# 780-00020_rev_2_pg1_Two_Axis_Stepper_Dri.net
KiCad netlist of a schematic drawn in Altium Designer
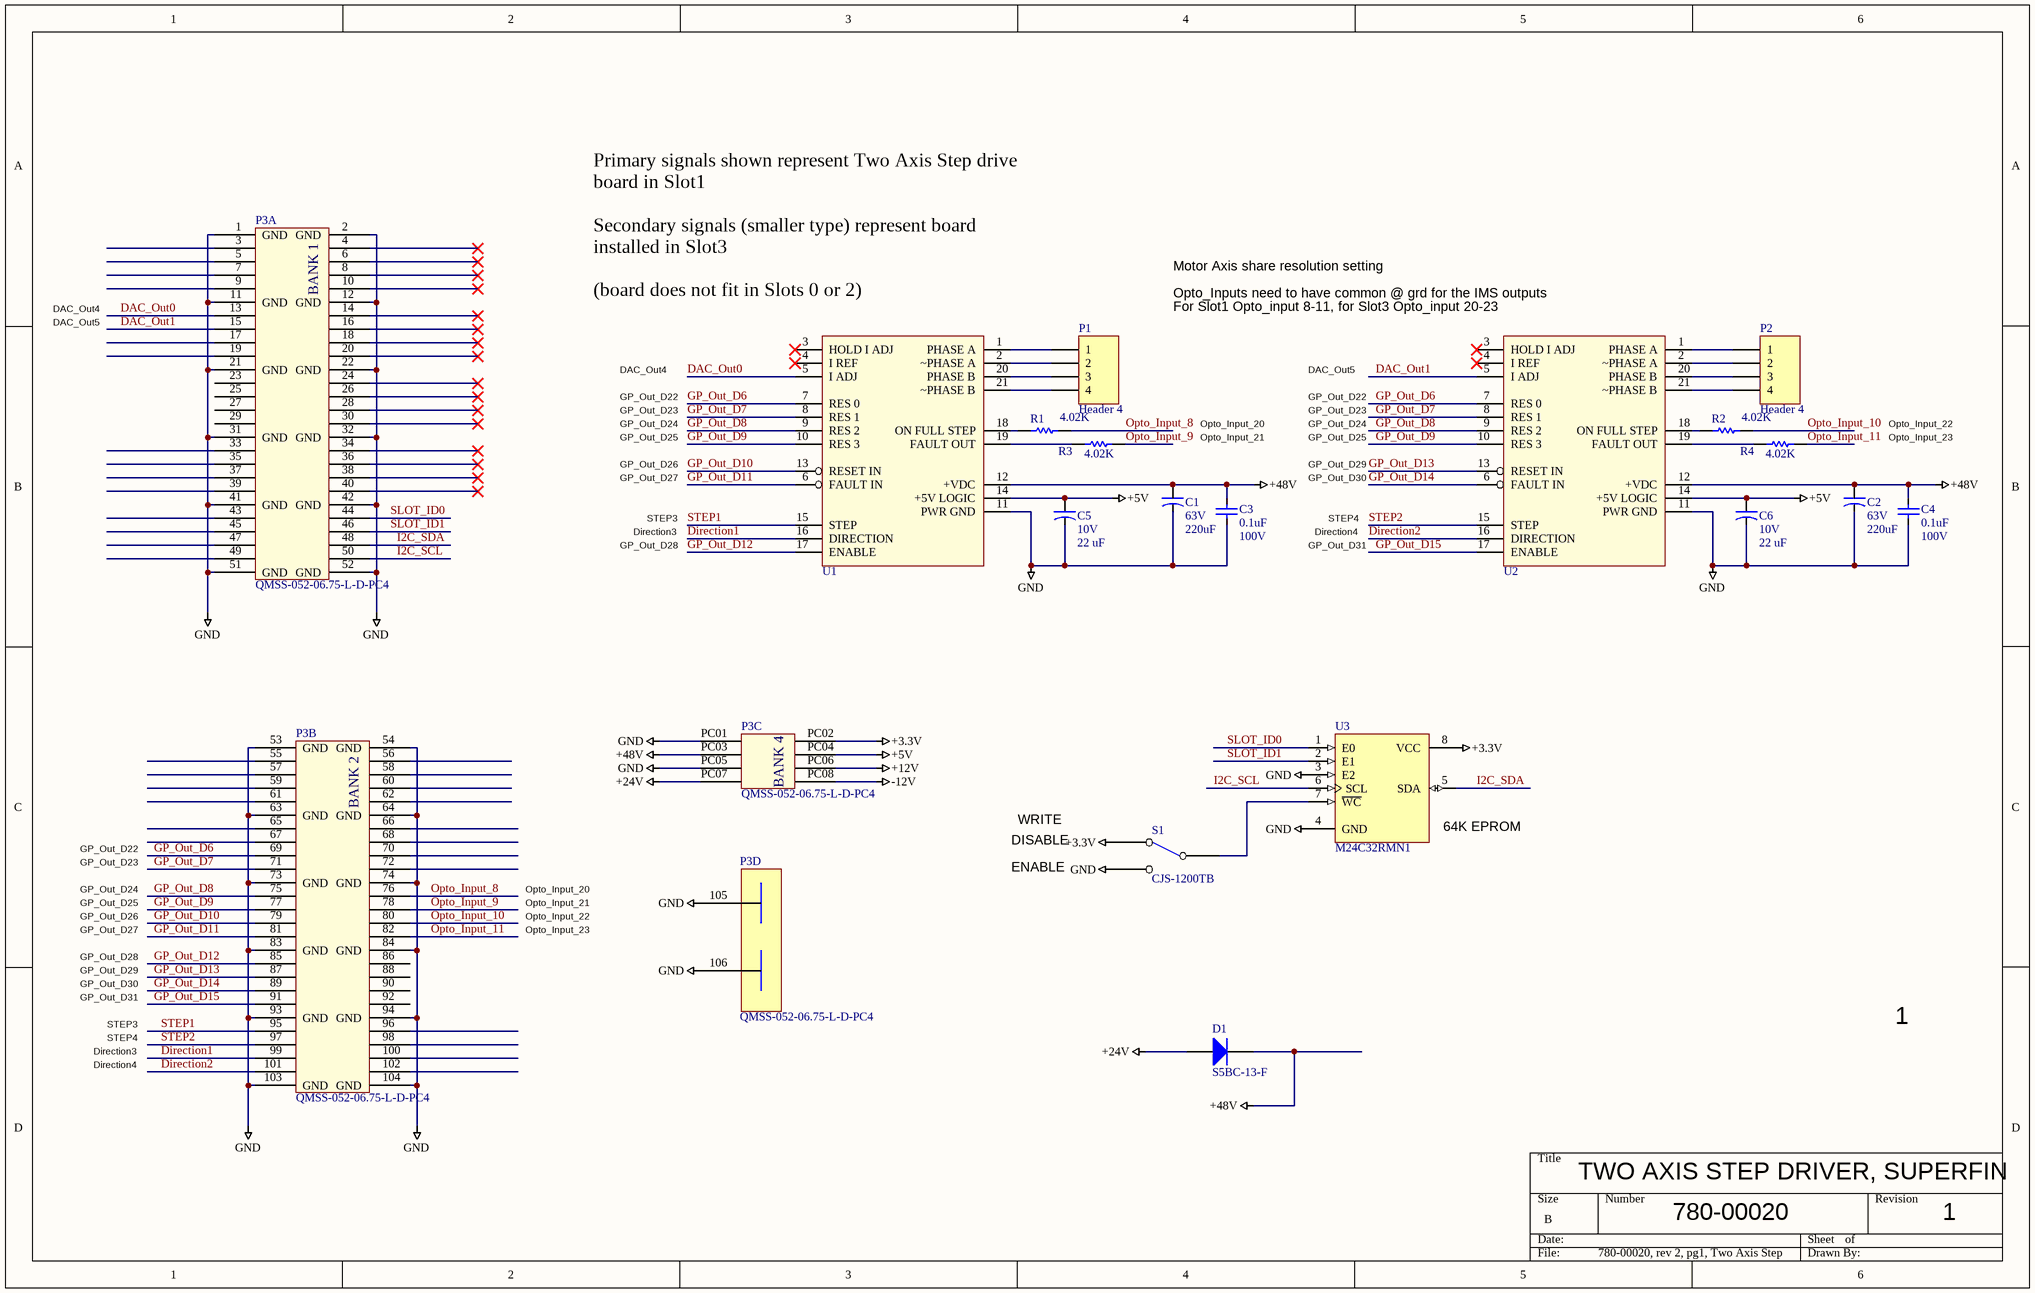
[diagram p0: 780-00020, rev 2, pg1, Two Axis Stepper Driver_old.SchDoc]

(export (version "E")
  (design (tool "Eeschema 10.0.6"))
  (components
    (comp (ref "C1")
      (value "63V")
      (footprint "CAP 220uF 63V")
      (description "CAP 220UF 63V ELECT MVH SMD")
      (fields (field (name "MANUFACTURER") "United Chemi-Con") (field (name "ALTIUM_VALUE") "220uF"))
      (libsource (lib "Richs Schematic Components") (part "Cap 220uF, 63V"))
    )
    (comp (ref "C2")
      (value "63V")
      (footprint "CAP 220uF 63V")
      (description "CAP 220UF 63V ELECT MVH SMD")
      (fields (field (name "MANUFACTURER") "United Chemi-Con") (field (name "ALTIUM_VALUE") "220uF"))
      (libsource (lib "Richs Schematic Components") (part "Cap 220uF, 63V"))
    )
    (comp (ref "C3")
      (value "100V")
      (footprint "SMD_0805")
      (description "Capacitor")
      (fields (field (name "MANUFACTURER") "TDK") (field (name "ALTIUM_VALUE") "0.1uF"))
      (libsource (lib "Richs Schematic Components") (part "Cap SMD"))
    )
    (comp (ref "C4")
      (value "100V")
      (footprint "SMD_0805")
      (description "Capacitor")
      (fields (field (name "MANUFACTURER") "TDK") (field (name "ALTIUM_VALUE") "0.1uF"))
      (libsource (lib "Richs Schematic Components") (part "Cap SMD"))
    )
    (comp (ref "C5")
      (value "10V")
      (footprint "SMD_CAP_3216")
      (description "outline 3.2mm x 1.6mm")
      (fields (field (name "MANUFACTURER") "AVX") (field (name "ALTIUM_VALUE") "22 uF"))
      (libsource (lib "Richs Schematic Components") (part "Cap Tant 16V"))
    )
    (comp (ref "C6")
      (value "10V")
      (footprint "SMD_CAP_3216")
      (description "outline 3.2mm x 1.6mm")
      (fields (field (name "MANUFACTURER") "AVX") (field (name "ALTIUM_VALUE") "22 uF"))
      (libsource (lib "Richs Schematic Components") (part "Cap Tant 16V"))
    )
    (comp (ref "D1")
      (value "S5BC-13-F")
      (footprint "SMC")
      (description "RECTIFIER GPP SMD 100V 5A SMC")
      (fields (field (name "MANUFACTURER") "Diodes Inc"))
      (libsource (lib "Miscellaneous Devices") (part "Diode"))
    )
    (comp (ref "P1")
      (value "Header 4")
      (footprint "HDR1X4 for IDC")
      (description "Header, 4-Pin")
      (libsource (lib "Richs Schematic Components") (part "Header 4"))
    )
    (comp (ref "P2")
      (value "Header 4")
      (footprint "HDR1X4 for IDC")
      (description "Header, 4-Pin")
      (libsource (lib "Richs Schematic Components") (part "Header 4"))
    )
    (comp (ref "P3")
      (value "QMSS-052-06.75-L-D-PC4")
      (footprint "QMS SMD PWR PINS - 104PIN")
      (description "SAMTEC QMSS W/PWR PINS")
      (fields (field (name "MANUFACTURER") "SAMTEC"))
      (libsource (lib "Richs Schematic Components") (part "QMSS-PC4-104 pin"))
    )
    (comp (ref "R1")
      (value "4.02K")
      (footprint "SMD_0805")
      (description "Resistor 0805")
      (fields (field (name "MANUFACTURER") "Vishay/Dale") (field (name "Comment") "Res 0805"))
      (libsource (lib "Richs Schematic Components") (part "Res SMD"))
    )
    (comp (ref "R2")
      (value "4.02K")
      (footprint "SMD_0805")
      (description "Resistor 0805")
      (fields (field (name "MANUFACTURER") "Vishay/Dale") (field (name "Comment") "Res 0805"))
      (libsource (lib "Richs Schematic Components") (part "Res SMD"))
    )
    (comp (ref "R3")
      (value "4.02K")
      (footprint "SMD_0805")
      (description "Resistor 0805")
      (fields (field (name "MANUFACTURER") "Vishay/Dale") (field (name "Comment") "Res 0805"))
      (libsource (lib "Richs Schematic Components") (part "Res SMD"))
    )
    (comp (ref "R4")
      (value "4.02K")
      (footprint "SMD_0805")
      (description "Resistor 0805")
      (fields (field (name "MANUFACTURER") "Vishay/Dale") (field (name "Comment") "Res 0805"))
      (libsource (lib "Richs Schematic Components") (part "Res SMD"))
    )
    (comp (ref "S1")
      (value "CJS-1200TB")
      (footprint "CAS-120B")
      (fields (field (name "MANUFACTURER") "Copal Electronics"))
      (libsource (lib "JON_1_Library") (part "SW_SPDT_DOUG"))
    )
    (comp (ref "U1")
      (value "IM481H Plus")
      (footprint "IM481H Vertical")
      (description "Hybrid stepper motor driver")
      (libsource (lib "Richs Schematic Components") (part "IM481H Plus"))
    )
    (comp (ref "U2")
      (value "IM481H Plus")
      (footprint "IM481H Vertical")
      (description "Hybrid stepper motor driver")
      (libsource (lib "Richs Schematic Components") (part "IM481H Plus"))
    )
    (comp (ref "U3")
      (value "M24C32RMN1")
      (footprint "SOP8_N")
      (description "32 Kbit Serial I²C Bus EEPROM")
      (libsource (lib "ST Memory EEPROM Serial") (part "M24C32RMN1"))
    )
  )
  (nets
    (net (code "1") (name "+3.3V") (class "Default")
      (node (ref "P3") (pin "PC02") (pinfunction "PC02_PC02") (pintype "passive"))
      (node (ref "S1") (pin "3") (pinfunction "NC_3") (pintype "passive"))
      (node (ref "U3") (pin "8") (pinfunction "VCC_8") (pintype "power_in"))
    )
    (net (code "2") (name "+5V") (class "Default")
      (node (ref "C5") (pin "1") (pinfunction "1_1") (pintype "passive"))
      (node (ref "C6") (pin "1") (pinfunction "1_1") (pintype "passive"))
      (node (ref "P3") (pin "PC04") (pinfunction "PC04_PC04") (pintype "passive"))
      (node (ref "U1") (pin "14") (pinfunction "+5V_LOGIC_14") (pintype "passive"))
      (node (ref "U2") (pin "14") (pinfunction "+5V_LOGIC_14") (pintype "passive"))
    )
    (net (code "3") (name "+12V") (class "Default")
      (node (ref "P3") (pin "PC06") (pinfunction "PC06_PC06") (pintype "passive"))
    )
    (net (code "4") (name "+24V") (class "Default")
      (node (ref "D1") (pin "1") (pinfunction "A_1") (pintype "passive"))
      (node (ref "P3") (pin "PC07") (pinfunction "PC07_PC07") (pintype "passive"))
    )
    (net (code "5") (name "+48V") (class "Default")
      (node (ref "C1") (pin "1") (pinfunction "1_1") (pintype "passive"))
      (node (ref "C2") (pin "1") (pinfunction "1_1") (pintype "passive"))
      (node (ref "C3") (pin "2") (pinfunction "2_2") (pintype "passive"))
      (node (ref "C4") (pin "2") (pinfunction "2_2") (pintype "passive"))
      (node (ref "D1") (pin "2") (pinfunction "K_2") (pintype "passive"))
      (node (ref "P3") (pin "PC03") (pinfunction "PC03_PC03") (pintype "passive"))
      (node (ref "U1") (pin "12") (pinfunction "+VDC_12") (pintype "passive"))
      (node (ref "U2") (pin "12") (pinfunction "+VDC_12") (pintype "passive"))
    )
    (net (code "6") (name "-12V") (class "Default")
      (node (ref "P3") (pin "PC08") (pinfunction "PC08_PC08") (pintype "passive"))
    )
    (net (code "7") (name "/DAC_Out0") (class "Default")
      (node (ref "P3") (pin "13") (pinfunction "13_13") (pintype "passive"))
      (node (ref "U1") (pin "5") (pinfunction "I_ADJ_5") (pintype "passive"))
    )
    (net (code "8") (name "/DAC_Out1") (class "Default")
      (node (ref "P3") (pin "15") (pinfunction "15_15") (pintype "passive"))
      (node (ref "U2") (pin "5") (pinfunction "I_ADJ_5") (pintype "passive"))
    )
    (net (code "9") (name "/Direction1") (class "Default")
      (node (ref "P3") (pin "99") (pinfunction "99_99") (pintype "passive"))
      (node (ref "U1") (pin "16") (pinfunction "DIRECTION_16") (pintype "passive"))
    )
    (net (code "10") (name "/Direction2") (class "Default")
      (node (ref "P3") (pin "101") (pinfunction "101_101") (pintype "passive"))
      (node (ref "U2") (pin "16") (pinfunction "DIRECTION_16") (pintype "passive"))
    )
    (net (code "11") (name "/GP_Out_D6") (class "Default")
      (node (ref "P3") (pin "69") (pinfunction "69_69") (pintype "passive"))
      (node (ref "U1") (pin "7") (pinfunction "RES_0_7") (pintype "passive"))
      (node (ref "U2") (pin "7") (pinfunction "RES_0_7") (pintype "passive"))
    )
    (net (code "12") (name "/GP_Out_D7") (class "Default")
      (node (ref "P3") (pin "71") (pinfunction "71_71") (pintype "passive"))
      (node (ref "U1") (pin "8") (pinfunction "RES_1_8") (pintype "passive"))
      (node (ref "U2") (pin "8") (pinfunction "RES_1_8") (pintype "passive"))
    )
    (net (code "13") (name "/GP_Out_D8") (class "Default")
      (node (ref "P3") (pin "75") (pinfunction "75_75") (pintype "passive"))
      (node (ref "U1") (pin "9") (pinfunction "RES_2_9") (pintype "passive"))
      (node (ref "U2") (pin "9") (pinfunction "RES_2_9") (pintype "passive"))
    )
    (net (code "14") (name "/GP_Out_D9") (class "Default")
      (node (ref "P3") (pin "77") (pinfunction "77_77") (pintype "passive"))
      (node (ref "U1") (pin "10") (pinfunction "RES_3_10") (pintype "passive"))
      (node (ref "U2") (pin "10") (pinfunction "RES_3_10") (pintype "passive"))
    )
    (net (code "15") (name "/GP_Out_D10") (class "Default")
      (node (ref "P3") (pin "79") (pinfunction "79_79") (pintype "passive"))
      (node (ref "U1") (pin "13") (pinfunction "RESET_IN_13") (pintype "passive"))
    )
    (net (code "16") (name "/GP_Out_D11") (class "Default")
      (node (ref "P3") (pin "81") (pinfunction "81_81") (pintype "passive"))
      (node (ref "U1") (pin "6") (pinfunction "FAULT_IN_6") (pintype "passive"))
    )
    (net (code "17") (name "/GP_Out_D12") (class "Default")
      (node (ref "P3") (pin "85") (pinfunction "85_85") (pintype "passive"))
      (node (ref "U1") (pin "17") (pinfunction "ENABLE_17") (pintype "passive"))
    )
    (net (code "18") (name "/GP_Out_D13") (class "Default")
      (node (ref "P3") (pin "87") (pinfunction "87_87") (pintype "passive"))
      (node (ref "U2") (pin "13") (pinfunction "RESET_IN_13") (pintype "passive"))
    )
    (net (code "19") (name "/GP_Out_D14") (class "Default")
      (node (ref "P3") (pin "89") (pinfunction "89_89") (pintype "passive"))
      (node (ref "U2") (pin "6") (pinfunction "FAULT_IN_6") (pintype "passive"))
    )
    (net (code "20") (name "/GP_Out_D15") (class "Default")
      (node (ref "P3") (pin "91") (pinfunction "91_91") (pintype "passive"))
      (node (ref "U2") (pin "17") (pinfunction "ENABLE_17") (pintype "passive"))
    )
    (net (code "21") (name "/I2C_SCL") (class "Default")
      (node (ref "P3") (pin "50") (pinfunction "50_50") (pintype "passive"))
      (node (ref "U3") (pin "6") (pinfunction "SCL_6") (pintype "input"))
    )
    (net (code "22") (name "/I2C_SDA") (class "Default")
      (node (ref "P3") (pin "48") (pinfunction "48_48") (pintype "passive"))
      (node (ref "U3") (pin "5") (pinfunction "SDA_5") (pintype "bidirectional"))
    )
    (net (code "23") (name "/Opto_Input_8") (class "Default")
      (node (ref "P3") (pin "76") (pinfunction "76_76") (pintype "passive"))
      (node (ref "R1") (pin "2") (pinfunction "2_2") (pintype "passive"))
    )
    (net (code "24") (name "/Opto_Input_9") (class "Default")
      (node (ref "P3") (pin "78") (pinfunction "78_78") (pintype "passive"))
      (node (ref "R3") (pin "2") (pinfunction "2_2") (pintype "passive"))
    )
    (net (code "25") (name "/Opto_Input_10") (class "Default")
      (node (ref "P3") (pin "80") (pinfunction "80_80") (pintype "passive"))
      (node (ref "R2") (pin "2") (pinfunction "2_2") (pintype "passive"))
    )
    (net (code "26") (name "/Opto_Input_11") (class "Default")
      (node (ref "P3") (pin "82") (pinfunction "82_82") (pintype "passive"))
      (node (ref "R4") (pin "2") (pinfunction "2_2") (pintype "passive"))
    )
    (net (code "27") (name "/SLOT_ID0") (class "Default")
      (node (ref "P3") (pin "44") (pinfunction "44_44") (pintype "passive"))
      (node (ref "U3") (pin "1") (pinfunction "E0_1") (pintype "input"))
    )
    (net (code "28") (name "/SLOT_ID1") (class "Default")
      (node (ref "P3") (pin "46") (pinfunction "46_46") (pintype "passive"))
      (node (ref "U3") (pin "2") (pinfunction "E1_2") (pintype "input"))
    )
    (net (code "29") (name "/STEP1") (class "Default")
      (node (ref "P3") (pin "95") (pinfunction "95_95") (pintype "passive"))
      (node (ref "U1") (pin "15") (pinfunction "STEP_15") (pintype "passive"))
    )
    (net (code "30") (name "/STEP2") (class "Default")
      (node (ref "P3") (pin "97") (pinfunction "97_97") (pintype "passive"))
      (node (ref "U2") (pin "15") (pinfunction "STEP_15") (pintype "passive"))
    )
    (net (code "31") (name "GND") (class "Default")
      (node (ref "C1") (pin "2") (pinfunction "2_2") (pintype "passive"))
      (node (ref "C2") (pin "2") (pinfunction "2_2") (pintype "passive"))
      (node (ref "C3") (pin "1") (pinfunction "1_1") (pintype "passive"))
      (node (ref "C4") (pin "1") (pinfunction "1_1") (pintype "passive"))
      (node (ref "C5") (pin "2") (pinfunction "2_2") (pintype "passive"))
      (node (ref "C6") (pin "2") (pinfunction "2_2") (pintype "passive"))
      (node (ref "P3") (pin "1") (pinfunction "GND_1") (pintype "passive"))
      (node (ref "P3") (pin "103") (pinfunction "GND_103") (pintype "passive"))
      (node (ref "P3") (pin "104") (pinfunction "GND_104") (pintype "passive"))
      (node (ref "P3") (pin "105") (pinfunction "GND_105") (pintype "passive"))
      (node (ref "P3") (pin "106") (pinfunction "GND_106") (pintype "passive"))
      (node (ref "P3") (pin "11") (pinfunction "GND_11") (pintype "passive"))
      (node (ref "P3") (pin "12") (pinfunction "GND_12") (pintype "passive"))
      (node (ref "P3") (pin "2") (pinfunction "GND_2") (pintype "passive"))
      (node (ref "P3") (pin "21") (pinfunction "GND_21") (pintype "passive"))
      (node (ref "P3") (pin "22") (pinfunction "GND_22") (pintype "passive"))
      (node (ref "P3") (pin "31") (pinfunction "GND_31") (pintype "passive"))
      (node (ref "P3") (pin "32") (pinfunction "GND_32") (pintype "passive"))
      (node (ref "P3") (pin "41") (pinfunction "GND_41") (pintype "passive"))
      (node (ref "P3") (pin "42") (pinfunction "GND_42") (pintype "passive"))
      (node (ref "P3") (pin "51") (pinfunction "GND_51") (pintype "passive"))
      (node (ref "P3") (pin "52") (pinfunction "GND_52") (pintype "passive"))
      (node (ref "P3") (pin "53") (pinfunction "GND_53") (pintype "passive"))
      (node (ref "P3") (pin "54") (pinfunction "GND_54") (pintype "passive"))
      (node (ref "P3") (pin "63") (pinfunction "GND_63") (pintype "passive"))
      (node (ref "P3") (pin "64") (pinfunction "GND_64") (pintype "passive"))
      (node (ref "P3") (pin "73") (pinfunction "GND_73") (pintype "passive"))
      (node (ref "P3") (pin "74") (pinfunction "GND_74") (pintype "passive"))
      (node (ref "P3") (pin "83") (pinfunction "GND_83") (pintype "passive"))
      (node (ref "P3") (pin "84") (pinfunction "GND_84") (pintype "passive"))
      (node (ref "P3") (pin "93") (pinfunction "GND_93") (pintype "passive"))
      (node (ref "P3") (pin "94") (pinfunction "GND_94") (pintype "passive"))
      (node (ref "P3") (pin "PC01") (pinfunction "PC01_PC01") (pintype "passive"))
      (node (ref "P3") (pin "PC05") (pinfunction "PC05_PC05") (pintype "passive"))
      (node (ref "S1") (pin "1") (pinfunction "NO_1") (pintype "passive"))
      (node (ref "U1") (pin "11") (pinfunction "PWR_GND_11") (pintype "passive"))
      (node (ref "U2") (pin "11") (pinfunction "PWR_GND_11") (pintype "passive"))
      (node (ref "U3") (pin "3") (pinfunction "E2_3") (pintype "input"))
      (node (ref "U3") (pin "4") (pinfunction "GND_4") (pintype "power_in"))
    )
    (net (code "32") (name "Net-(S1-COM)") (class "Default")
      (node (ref "S1") (pin "2") (pinfunction "COM_2") (pintype "passive"))
      (node (ref "U3") (pin "7") (pinfunction "~{WC}_7") (pintype "input"))
    )
    (net (code "33") (name "Net-(U1-FAULT_OUT)") (class "Default")
      (node (ref "R3") (pin "1") (pinfunction "1_1") (pintype "passive"))
      (node (ref "U1") (pin "19") (pinfunction "FAULT_OUT_19") (pintype "passive"))
    )
    (net (code "34") (name "Net-(U1-ON_FULL_STEP)") (class "Default")
      (node (ref "R1") (pin "1") (pinfunction "1_1") (pintype "passive"))
      (node (ref "U1") (pin "18") (pinfunction "ON_FULL_STEP_18") (pintype "passive"))
    )
    (net (code "35") (name "Net-(U1-PHASE_A)") (class "Default")
      (node (ref "P1") (pin "1") (pinfunction "1_1") (pintype "passive"))
      (node (ref "U1") (pin "1") (pinfunction "PHASE_A_1") (pintype "passive"))
    )
    (net (code "36") (name "Net-(U1-PHASE_B)") (class "Default")
      (node (ref "P1") (pin "3") (pinfunction "3_3") (pintype "passive"))
      (node (ref "U1") (pin "20") (pinfunction "PHASE_B_20") (pintype "passive"))
    )
    (net (code "37") (name "Net-(U1-~PHASE_A)") (class "Default")
      (node (ref "P1") (pin "2") (pinfunction "2_2") (pintype "passive"))
      (node (ref "U1") (pin "2") (pinfunction "~PHASE_A_2") (pintype "passive"))
    )
    (net (code "38") (name "Net-(U1-~PHASE_B)") (class "Default")
      (node (ref "P1") (pin "4") (pinfunction "4_4") (pintype "passive"))
      (node (ref "U1") (pin "21") (pinfunction "~PHASE_B_21") (pintype "passive"))
    )
    (net (code "39") (name "Net-(U2-FAULT_OUT)") (class "Default")
      (node (ref "R4") (pin "1") (pinfunction "1_1") (pintype "passive"))
      (node (ref "U2") (pin "19") (pinfunction "FAULT_OUT_19") (pintype "passive"))
    )
    (net (code "40") (name "Net-(U2-ON_FULL_STEP)") (class "Default")
      (node (ref "R2") (pin "1") (pinfunction "1_1") (pintype "passive"))
      (node (ref "U2") (pin "18") (pinfunction "ON_FULL_STEP_18") (pintype "passive"))
    )
    (net (code "41") (name "Net-(U2-PHASE_A)") (class "Default")
      (node (ref "P2") (pin "1") (pinfunction "1_1") (pintype "passive"))
      (node (ref "U2") (pin "1") (pinfunction "PHASE_A_1") (pintype "passive"))
    )
    (net (code "42") (name "Net-(U2-PHASE_B)") (class "Default")
      (node (ref "P2") (pin "3") (pinfunction "3_3") (pintype "passive"))
      (node (ref "U2") (pin "20") (pinfunction "PHASE_B_20") (pintype "passive"))
    )
    (net (code "43") (name "Net-(U2-~PHASE_A)") (class "Default")
      (node (ref "P2") (pin "2") (pinfunction "2_2") (pintype "passive"))
      (node (ref "U2") (pin "2") (pinfunction "~PHASE_A_2") (pintype "passive"))
    )
    (net (code "44") (name "Net-(U2-~PHASE_B)") (class "Default")
      (node (ref "P2") (pin "4") (pinfunction "4_4") (pintype "passive"))
      (node (ref "U2") (pin "21") (pinfunction "~PHASE_B_21") (pintype "passive"))
    )
    (net (code "45") (name "unconnected-(P3-Pad3)") (class "Default")
      (node (ref "P3") (pin "3") (pinfunction "3_3") (pintype "passive"))
    )
    (net (code "46") (name "unconnected-(P3-Pad4)") (class "Default")
      (node (ref "P3") (pin "4") (pinfunction "4_4") (pintype "passive+no_connect"))
    )
    (net (code "47") (name "unconnected-(P3-Pad5)") (class "Default")
      (node (ref "P3") (pin "5") (pinfunction "5_5") (pintype "passive"))
    )
    (net (code "48") (name "unconnected-(P3-Pad6)") (class "Default")
      (node (ref "P3") (pin "6") (pinfunction "6_6") (pintype "passive+no_connect"))
    )
    (net (code "49") (name "unconnected-(P3-Pad7)") (class "Default")
      (node (ref "P3") (pin "7") (pinfunction "7_7") (pintype "passive"))
    )
    (net (code "50") (name "unconnected-(P3-Pad8)") (class "Default")
      (node (ref "P3") (pin "8") (pinfunction "8_8") (pintype "passive+no_connect"))
    )
    (net (code "51") (name "unconnected-(P3-Pad9)") (class "Default")
      (node (ref "P3") (pin "9") (pinfunction "9_9") (pintype "passive"))
    )
    (net (code "52") (name "unconnected-(P3-Pad10)") (class "Default")
      (node (ref "P3") (pin "10") (pinfunction "10_10") (pintype "passive+no_connect"))
    )
    (net (code "53") (name "unconnected-(P3-Pad14)") (class "Default")
      (node (ref "P3") (pin "14") (pinfunction "14_14") (pintype "passive+no_connect"))
    )
    (net (code "54") (name "unconnected-(P3-Pad16)") (class "Default")
      (node (ref "P3") (pin "16") (pinfunction "16_16") (pintype "passive+no_connect"))
    )
    (net (code "55") (name "unconnected-(P3-Pad17)") (class "Default")
      (node (ref "P3") (pin "17") (pinfunction "17_17") (pintype "passive"))
    )
    (net (code "56") (name "unconnected-(P3-Pad18)") (class "Default")
      (node (ref "P3") (pin "18") (pinfunction "18_18") (pintype "passive+no_connect"))
    )
    (net (code "57") (name "unconnected-(P3-Pad19)") (class "Default")
      (node (ref "P3") (pin "19") (pinfunction "19_19") (pintype "passive"))
    )
    (net (code "58") (name "unconnected-(P3-Pad20)") (class "Default")
      (node (ref "P3") (pin "20") (pinfunction "20_20") (pintype "passive+no_connect"))
    )
    (net (code "59") (name "unconnected-(P3-Pad23)") (class "Default")
      (node (ref "P3") (pin "23") (pinfunction "23_23") (pintype "passive"))
    )
    (net (code "60") (name "unconnected-(P3-Pad24)") (class "Default")
      (node (ref "P3") (pin "24") (pinfunction "24_24") (pintype "passive+no_connect"))
    )
    (net (code "61") (name "unconnected-(P3-Pad25)") (class "Default")
      (node (ref "P3") (pin "25") (pinfunction "25_25") (pintype "passive"))
    )
    (net (code "62") (name "unconnected-(P3-Pad26)") (class "Default")
      (node (ref "P3") (pin "26") (pinfunction "26_26") (pintype "passive+no_connect"))
    )
    (net (code "63") (name "unconnected-(P3-Pad27)") (class "Default")
      (node (ref "P3") (pin "27") (pinfunction "27_27") (pintype "passive"))
    )
    (net (code "64") (name "unconnected-(P3-Pad28)") (class "Default")
      (node (ref "P3") (pin "28") (pinfunction "28_28") (pintype "passive+no_connect"))
    )
    (net (code "65") (name "unconnected-(P3-Pad29)") (class "Default")
      (node (ref "P3") (pin "29") (pinfunction "29_29") (pintype "passive"))
    )
    (net (code "66") (name "unconnected-(P3-Pad30)") (class "Default")
      (node (ref "P3") (pin "30") (pinfunction "30_30") (pintype "passive+no_connect"))
    )
    (net (code "67") (name "unconnected-(P3-Pad33)") (class "Default")
      (node (ref "P3") (pin "33") (pinfunction "33_33") (pintype "passive"))
    )
    (net (code "68") (name "unconnected-(P3-Pad34)") (class "Default")
      (node (ref "P3") (pin "34") (pinfunction "34_34") (pintype "passive+no_connect"))
    )
    (net (code "69") (name "unconnected-(P3-Pad35)") (class "Default")
      (node (ref "P3") (pin "35") (pinfunction "35_35") (pintype "passive"))
    )
    (net (code "70") (name "unconnected-(P3-Pad36)") (class "Default")
      (node (ref "P3") (pin "36") (pinfunction "36_36") (pintype "passive+no_connect"))
    )
    (net (code "71") (name "unconnected-(P3-Pad37)") (class "Default")
      (node (ref "P3") (pin "37") (pinfunction "37_37") (pintype "passive"))
    )
    (net (code "72") (name "unconnected-(P3-Pad38)") (class "Default")
      (node (ref "P3") (pin "38") (pinfunction "38_38") (pintype "passive+no_connect"))
    )
    (net (code "73") (name "unconnected-(P3-Pad39)") (class "Default")
      (node (ref "P3") (pin "39") (pinfunction "39_39") (pintype "passive"))
    )
    (net (code "74") (name "unconnected-(P3-Pad40)") (class "Default")
      (node (ref "P3") (pin "40") (pinfunction "40_40") (pintype "passive+no_connect"))
    )
    (net (code "75") (name "unconnected-(P3-Pad43)") (class "Default")
      (node (ref "P3") (pin "43") (pinfunction "43_43") (pintype "passive"))
    )
    (net (code "76") (name "unconnected-(P3-Pad45)") (class "Default")
      (node (ref "P3") (pin "45") (pinfunction "45_45") (pintype "passive"))
    )
    (net (code "77") (name "unconnected-(P3-Pad47)") (class "Default")
      (node (ref "P3") (pin "47") (pinfunction "47_47") (pintype "passive"))
    )
    (net (code "78") (name "unconnected-(P3-Pad49)") (class "Default")
      (node (ref "P3") (pin "49") (pinfunction "49_49") (pintype "passive"))
    )
    (net (code "79") (name "unconnected-(P3-Pad55)") (class "Default")
      (node (ref "P3") (pin "55") (pinfunction "55_55") (pintype "passive"))
    )
    (net (code "80") (name "unconnected-(P3-Pad56)") (class "Default")
      (node (ref "P3") (pin "56") (pinfunction "56_56") (pintype "passive"))
    )
    (net (code "81") (name "unconnected-(P3-Pad57)") (class "Default")
      (node (ref "P3") (pin "57") (pinfunction "57_57") (pintype "passive"))
    )
    (net (code "82") (name "unconnected-(P3-Pad58)") (class "Default")
      (node (ref "P3") (pin "58") (pinfunction "58_58") (pintype "passive"))
    )
    (net (code "83") (name "unconnected-(P3-Pad59)") (class "Default")
      (node (ref "P3") (pin "59") (pinfunction "59_59") (pintype "passive"))
    )
    (net (code "84") (name "unconnected-(P3-Pad60)") (class "Default")
      (node (ref "P3") (pin "60") (pinfunction "60_60") (pintype "passive"))
    )
    (net (code "85") (name "unconnected-(P3-Pad61)") (class "Default")
      (node (ref "P3") (pin "61") (pinfunction "61_61") (pintype "passive"))
    )
    (net (code "86") (name "unconnected-(P3-Pad62)") (class "Default")
      (node (ref "P3") (pin "62") (pinfunction "62_62") (pintype "passive"))
    )
    (net (code "87") (name "unconnected-(P3-Pad65)") (class "Default")
      (node (ref "P3") (pin "65") (pinfunction "65_65") (pintype "passive"))
    )
    (net (code "88") (name "unconnected-(P3-Pad66)") (class "Default")
      (node (ref "P3") (pin "66") (pinfunction "66_66") (pintype "passive"))
    )
    (net (code "89") (name "unconnected-(P3-Pad67)") (class "Default")
      (node (ref "P3") (pin "67") (pinfunction "67_67") (pintype "passive"))
    )
    (net (code "90") (name "unconnected-(P3-Pad68)") (class "Default")
      (node (ref "P3") (pin "68") (pinfunction "68_68") (pintype "passive"))
    )
    (net (code "91") (name "unconnected-(P3-Pad70)") (class "Default")
      (node (ref "P3") (pin "70") (pinfunction "70_70") (pintype "passive"))
    )
    (net (code "92") (name "unconnected-(P3-Pad72)") (class "Default")
      (node (ref "P3") (pin "72") (pinfunction "72_72") (pintype "passive"))
    )
    (net (code "93") (name "unconnected-(P3-Pad86)") (class "Default")
      (node (ref "P3") (pin "86") (pinfunction "86_86") (pintype "passive"))
    )
    (net (code "94") (name "unconnected-(P3-Pad88)") (class "Default")
      (node (ref "P3") (pin "88") (pinfunction "88_88") (pintype "passive"))
    )
    (net (code "95") (name "unconnected-(P3-Pad90)") (class "Default")
      (node (ref "P3") (pin "90") (pinfunction "90_90") (pintype "passive"))
    )
    (net (code "96") (name "unconnected-(P3-Pad92)") (class "Default")
      (node (ref "P3") (pin "92") (pinfunction "92_92") (pintype "passive"))
    )
    (net (code "97") (name "unconnected-(P3-Pad96)") (class "Default")
      (node (ref "P3") (pin "96") (pinfunction "96_96") (pintype "passive"))
    )
    (net (code "98") (name "unconnected-(P3-Pad98)") (class "Default")
      (node (ref "P3") (pin "98") (pinfunction "98_98") (pintype "passive"))
    )
    (net (code "99") (name "unconnected-(P3-Pad100)") (class "Default")
      (node (ref "P3") (pin "100") (pinfunction "100_100") (pintype "passive"))
    )
    (net (code "100") (name "unconnected-(P3-Pad102)") (class "Default")
      (node (ref "P3") (pin "102") (pinfunction "102_102") (pintype "passive"))
    )
    (net (code "101") (name "unconnected-(U1-HOLD_I_ADJ-Pad3)") (class "Default")
      (node (ref "U1") (pin "3") (pinfunction "HOLD_I_ADJ_3") (pintype "passive+no_connect"))
    )
    (net (code "102") (name "unconnected-(U1-I_REF-Pad4)") (class "Default")
      (node (ref "U1") (pin "4") (pinfunction "I_REF_4") (pintype "passive+no_connect"))
    )
    (net (code "103") (name "unconnected-(U2-HOLD_I_ADJ-Pad3)") (class "Default")
      (node (ref "U2") (pin "3") (pinfunction "HOLD_I_ADJ_3") (pintype "passive+no_connect"))
    )
    (net (code "104") (name "unconnected-(U2-I_REF-Pad4)") (class "Default")
      (node (ref "U2") (pin "4") (pinfunction "I_REF_4") (pintype "passive+no_connect"))
    )
  )
)
